# bk-circ2-S.net
KiCad netlist of a schematic drawn in EAGLE
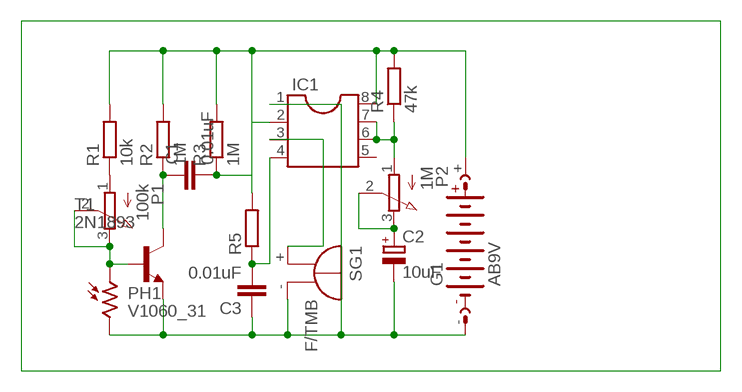
[diagram p0: schematic, sheet 1]

(export (version "E")
  (design (tool "Eeschema 10.0.6"))
  (components
    (comp (ref "C1")
      (value "0.01uF")
      (footprint "eagle-import:C050-025X075")
      (libsource (lib "eagle-import") (part "C-EU050-025X075"))
    )
    (comp (ref "C2")
      (value "10uF")
      (footprint "eagle-import:B45181B")
      (libsource (lib "eagle-import") (part "CPOL-EUB45181B"))
    )
    (comp (ref "C3")
      (value "0.01uF")
      (footprint "eagle-import:C050-025X075")
      (libsource (lib "eagle-import") (part "C-EU050-025X075"))
    )
    (comp (ref "G1")
      (value "AB9V")
      (footprint "eagle-import:AB9V")
      (libsource (lib "eagle-import") (part "AB9V"))
    )
    (comp (ref "IC1")
      (value "DIL8")
      (footprint "eagle-import:DIL08")
      (libsource (lib "eagle-import") (part "DIL8"))
    )
    (comp (ref "P1")
      (value "100k")
      (footprint "eagle-import:3RP_1610N")
      (libsource (lib "eagle-import") (part "3RP/1610N"))
    )
    (comp (ref "P2")
      (value "1M")
      (footprint "eagle-import:3RP_1610N")
      (libsource (lib "eagle-import") (part "3RP/1610N"))
    )
    (comp (ref "PH1")
      (value "V1060_31")
      (footprint "eagle-import:TO-5_V10")
      (libsource (lib "eagle-import") (part "?1060V_31"))
    )
    (comp (ref "R1")
      (value "10k")
      (footprint "eagle-import:0207_7")
      (libsource (lib "eagle-import") (part "R-EU_0207/7"))
    )
    (comp (ref "R2")
      (value "1M")
      (footprint "eagle-import:0207_7")
      (libsource (lib "eagle-import") (part "R-EU_0207/7"))
    )
    (comp (ref "R3")
      (value "1M")
      (footprint "eagle-import:0207_7")
      (libsource (lib "eagle-import") (part "R-EU_0207/7"))
    )
    (comp (ref "R4")
      (value "47k")
      (footprint "eagle-import:0207_7")
      (libsource (lib "eagle-import") (part "R-EU_0207/7"))
    )
    (comp (ref "R5")
      (value "R-EU_0207/7")
      (footprint "eagle-import:0207_7")
      (libsource (lib "eagle-import") (part "R-EU_0207/7"))
    )
    (comp (ref "SG1")
      (value "F/TMB")
      (footprint "eagle-import:F_TMB")
      (libsource (lib "eagle-import") (part "F/TMB"))
    )
    (comp (ref "T1")
      (value "2N1893")
      (footprint "eagle-import:TO5")
      (libsource (lib "eagle-import") (part "2N1893"))
    )
  )
  (nets
    (net (code "1") (name "Net-(C1-Pad2)") (class "Default")
      (node (ref "C1") (pin "2") (pinfunction "2_2") (pintype "passive"))
      (node (ref "IC1") (pin "2") (pinfunction "2_2") (pintype "passive"))
      (node (ref "R3") (pin "1") (pinfunction "1_1") (pintype "passive"))
    )
    (net (code "2") (name "Net-(C3-Pad2)") (class "Default")
      (node (ref "C3") (pin "2") (pinfunction "2_2") (pintype "passive"))
      (node (ref "IC1") (pin "4") (pinfunction "4_4") (pintype "passive"))
      (node (ref "R5") (pin "1") (pinfunction "1_1") (pintype "passive"))
    )
    (net (code "3") (name "Net-(G1-Pad+)") (class "Default")
      (node (ref "G1") (pin "+") (pinfunction "+_+") (pintype "passive"))
      (node (ref "IC1") (pin "8") (pinfunction "8_8") (pintype "passive"))
      (node (ref "R1") (pin "2") (pinfunction "2_2") (pintype "passive"))
      (node (ref "R2") (pin "2") (pinfunction "2_2") (pintype "passive"))
      (node (ref "R3") (pin "2") (pinfunction "2_2") (pintype "passive"))
      (node (ref "R4") (pin "2") (pinfunction "2_2") (pintype "passive"))
      (node (ref "R5") (pin "2") (pinfunction "2_2") (pintype "passive"))
    )
    (net (code "4") (name "Net-(IC1-Pad3)") (class "Default")
      (node (ref "IC1") (pin "3") (pinfunction "3_3") (pintype "passive"))
      (node (ref "SG1") (pin "+") (pinfunction "+_+") (pintype "passive"))
    )
    (net (code "5") (name "Net-(P1-A)") (class "Default")
      (node (ref "P1") (pin "1") (pinfunction "A_1") (pintype "passive"))
      (node (ref "R1") (pin "1") (pinfunction "1_1") (pintype "passive"))
    )
    (net (code "6") (name "Net-(P1-E)") (class "Default")
      (node (ref "P1") (pin "2") (pinfunction "S_2") (pintype "passive"))
      (node (ref "P1") (pin "3") (pinfunction "E_3") (pintype "passive"))
      (node (ref "PH1") (pin "1") (pinfunction "1_1") (pintype "passive"))
      (node (ref "T1") (pin "2") (pinfunction "B_2") (pintype "passive"))
    )
    (net (code "7") (name "Net-(P2-A)") (class "Default")
      (node (ref "IC1") (pin "6") (pinfunction "6_6") (pintype "passive"))
      (node (ref "IC1") (pin "7") (pinfunction "7_7") (pintype "passive"))
      (node (ref "P2") (pin "1") (pinfunction "A_1") (pintype "passive"))
      (node (ref "R4") (pin "1") (pinfunction "1_1") (pintype "passive"))
    )
    (net (code "8") (name "Net-(P2-E)") (class "Default")
      (node (ref "C2") (pin "+") (pinfunction "+_+") (pintype "passive"))
      (node (ref "P2") (pin "2") (pinfunction "S_2") (pintype "passive"))
      (node (ref "P2") (pin "3") (pinfunction "E_3") (pintype "passive"))
    )
    (net (code "9") (name "Net-(T1-C)") (class "Default")
      (node (ref "C1") (pin "1") (pinfunction "1_1") (pintype "passive"))
      (node (ref "R2") (pin "1") (pinfunction "1_1") (pintype "passive"))
      (node (ref "T1") (pin "3") (pinfunction "C_3") (pintype "passive"))
    )
    (net (code "10") (name "Net-(T1-E)") (class "Default")
      (node (ref "C2") (pin "-") (pinfunction "-_-") (pintype "passive"))
      (node (ref "C3") (pin "1") (pinfunction "1_1") (pintype "passive"))
      (node (ref "G1") (pin "-") (pinfunction "-_-") (pintype "passive"))
      (node (ref "IC1") (pin "1") (pinfunction "1_1") (pintype "passive"))
      (node (ref "PH1") (pin "2") (pinfunction "2_2") (pintype "passive"))
      (node (ref "SG1") (pin "-") (pinfunction "-_-") (pintype "passive"))
      (node (ref "T1") (pin "1") (pinfunction "E_1") (pintype "passive"))
    )
    (net (code "11") (name "unconnected-(IC1-Pad5)") (class "Default")
      (node (ref "IC1") (pin "5") (pinfunction "5_5") (pintype "passive"))
    )
  )
)
